# templog2.net
KiCad netlist of a schematic drawn in EAGLE
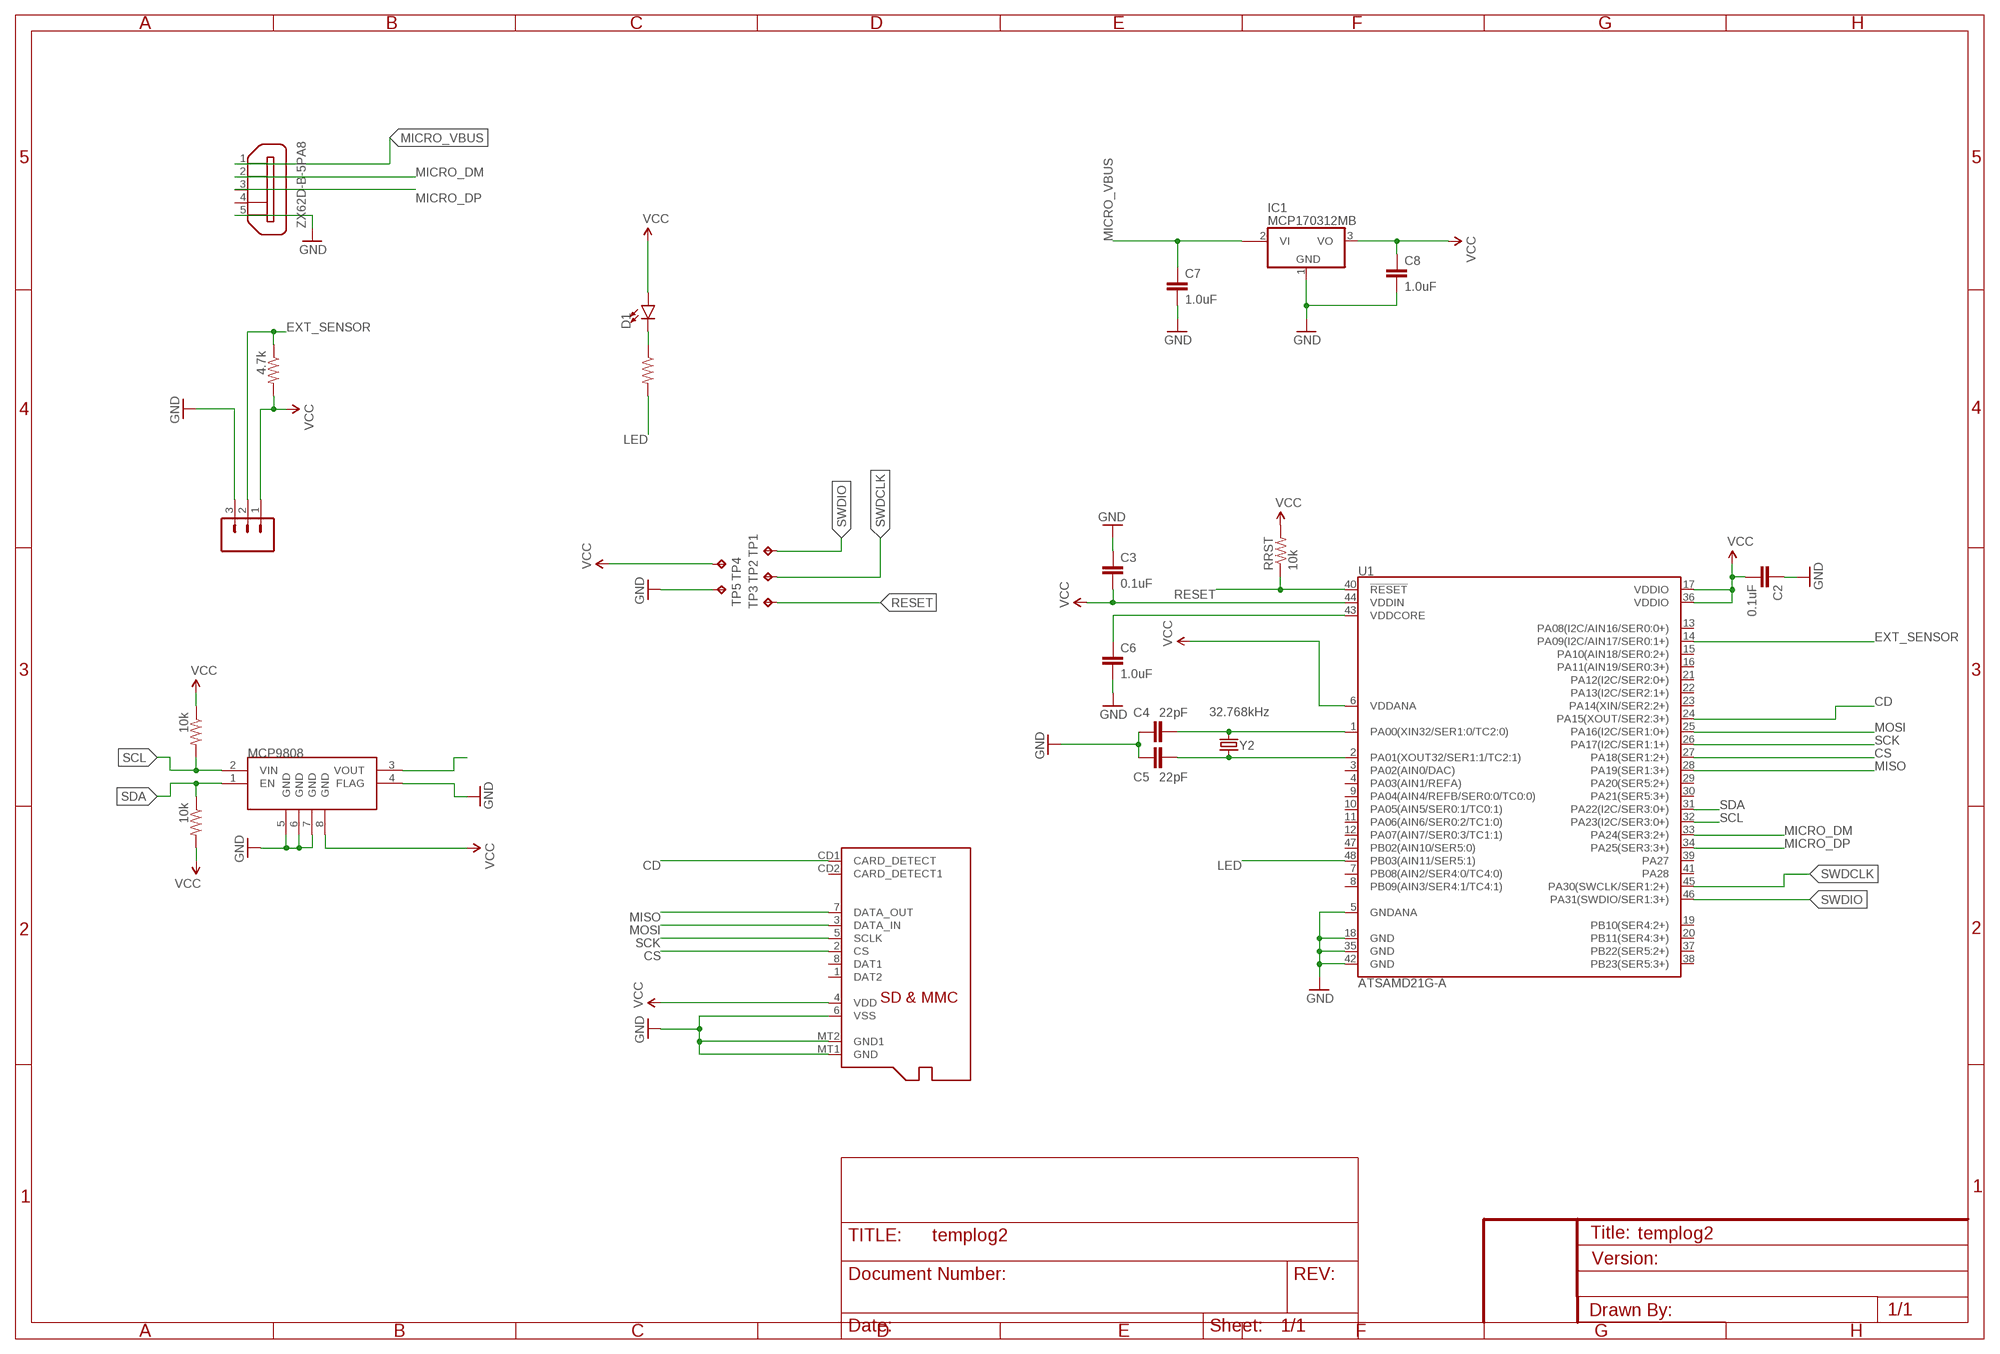
[diagram p0: schematic, sheet 1]

(export (version "E")
  (design (tool "Eeschema 10.0.6"))
  (components
    (comp (ref "C2")
      (value "0.1uF")
      (footprint "eagle-import:0805")
      (libsource (lib "eagle-import") (part "1.0UF-0805-25V-10%"))
    )
    (comp (ref "C3")
      (value "0.1uF")
      (footprint "eagle-import:0805")
      (libsource (lib "eagle-import") (part "1.0UF-0805-25V-10%"))
    )
    (comp (ref "C4")
      (value "22pF")
      (footprint "eagle-import:0805")
      (libsource (lib "eagle-import") (part "CAP0805"))
    )
    (comp (ref "C5")
      (value "22pF")
      (footprint "eagle-import:0805")
      (libsource (lib "eagle-import") (part "CAP0805"))
    )
    (comp (ref "C6")
      (value "1.0uF")
      (footprint "eagle-import:0805")
      (libsource (lib "eagle-import") (part "1.0UF-0805-25V-10%"))
    )
    (comp (ref "C7")
      (value "1.0uF")
      (footprint "eagle-import:0805")
      (libsource (lib "eagle-import") (part "1.0UF-0805-25V-10%"))
    )
    (comp (ref "C8")
      (value "1.0uF")
      (footprint "eagle-import:0805")
      (libsource (lib "eagle-import") (part "1.0UF-0805-25V-10%"))
    )
    (comp (ref "D1")
      (value "LED1206")
      (footprint "eagle-import:LED-1206")
      (libsource (lib "eagle-import") (part "LED1206"))
    )
    (comp (ref "IC1")
      (value "MCP170312MB")
      (footprint "eagle-import:SOT89")
      (libsource (lib "eagle-import") (part "MCP1703MB12"))
    )
    (comp (ref "J2")
      (value "CONN_03SMD")
      (footprint "eagle-import:1X03-1MM-RA")
      (libsource (lib "eagle-import") (part "CONN_03SMD"))
    )
    (comp (ref "MCP9808")
      (value "V_REG_MIC5216")
      (footprint "eagle-import:MSOP8")
      (libsource (lib "eagle-import") (part "V_REG_MIC5216"))
    )
    (comp (ref "RRST")
      (value "10k")
      (footprint "eagle-import:0805")
      (libsource (lib "eagle-import") (part "RESISTOR0805-RES"))
    )
    (comp (ref "R_I2C_1")
      (value "10k")
      (footprint "eagle-import:0805")
      (libsource (lib "eagle-import") (part "RESISTOR0805-RES"))
    )
    (comp (ref "R_I2C_2")
      (value "10k")
      (footprint "eagle-import:0805")
      (libsource (lib "eagle-import") (part "RESISTOR0805-RES"))
    )
    (comp (ref "R_I2C_3")
      (value "4.7k")
      (footprint "eagle-import:0805")
      (libsource (lib "eagle-import") (part "RESISTOR0805-RES"))
    )
    (comp (ref "R_I2C_4")
      (value "RESISTOR0805-RES")
      (footprint "eagle-import:0805")
      (libsource (lib "eagle-import") (part "RESISTOR0805-RES"))
    )
    (comp (ref "TP1")
      (value "TPB1,27")
      (footprint "eagle-import:B1,27")
      (libsource (lib "eagle-import") (part "TPB1,27"))
    )
    (comp (ref "TP2")
      (value "TPB1,27")
      (footprint "eagle-import:B1,27")
      (libsource (lib "eagle-import") (part "TPB1,27"))
    )
    (comp (ref "TP3")
      (value "TPB1,27")
      (footprint "eagle-import:B1,27")
      (libsource (lib "eagle-import") (part "TPB1,27"))
    )
    (comp (ref "TP4")
      (value "TPB1,27")
      (footprint "eagle-import:B1,27")
      (libsource (lib "eagle-import") (part "TPB1,27"))
    )
    (comp (ref "TP5")
      (value "TPB1,27")
      (footprint "eagle-import:B1,27")
      (libsource (lib "eagle-import") (part "TPB1,27"))
    )
    (comp (ref "U$1")
      (value "MICROSD")
      (footprint "eagle-import:MICROSD")
      (libsource (lib "eagle-import") (part "MICROSD"))
    )
    (comp (ref "U1")
      (value "ATSAMD21G-A")
      (footprint "eagle-import:TQFP-48")
      (libsource (lib "eagle-import") (part "ATSAMD21G-A"))
    )
    (comp (ref "X2")
      (value "ZX62D-B-5PA8")
      (footprint "eagle-import:ZX62D-B-5PA8")
      (fields (field (name "MF") "Hirose"))
      (libsource (lib "eagle-import") (part "ZX62D-B-5PA8"))
    )
    (comp (ref "Y2")
      (value "32.768kHz")
      (footprint "eagle-import:CRYSTAL-SMD-3.2X1.5MM")
      (libsource (lib "eagle-import") (part "CRYSTAL3.2X1.5MM"))
    )
  )
  (nets
    (net (code "1") (name "/CD") (class "Default")
      (node (ref "U$1") (pin "CD1") (pinfunction "CARD_DETECT_CD1") (pintype "passive"))
      (node (ref "U1") (pin "24") (pinfunction "PA15(XOUT/SER2:3+)_24") (pintype "bidirectional"))
    )
    (net (code "2") (name "/CS") (class "Default")
      (node (ref "U$1") (pin "2") (pinfunction "CS_2") (pintype "input"))
      (node (ref "U1") (pin "27") (pinfunction "PA18(SER1:2+)_27") (pintype "bidirectional"))
    )
    (net (code "3") (name "/EXT_SENSOR") (class "Default")
      (node (ref "J2") (pin "2") (pinfunction "2_2") (pintype "passive"))
      (node (ref "R_I2C_3") (pin "1") (pinfunction "1_1") (pintype "passive"))
      (node (ref "U1") (pin "14") (pinfunction "PA09(I2C/AIN17/SER0:1+)_14") (pintype "bidirectional"))
    )
    (net (code "4") (name "/LED") (class "Default")
      (node (ref "R_I2C_4") (pin "2") (pinfunction "2_2") (pintype "passive"))
      (node (ref "U1") (pin "48") (pinfunction "PB03(AIN11/SER5:1)_48") (pintype "bidirectional"))
    )
    (net (code "5") (name "/MICRO_DM") (class "Default")
      (node (ref "U1") (pin "33") (pinfunction "PA24(SER3:2+)_33") (pintype "bidirectional"))
      (node (ref "X2") (pin "2") (pinfunction "2_2") (pintype "passive"))
    )
    (net (code "6") (name "/MICRO_DP") (class "Default")
      (node (ref "U1") (pin "34") (pinfunction "PA25(SER3:3+)_34") (pintype "bidirectional"))
      (node (ref "X2") (pin "3") (pinfunction "3_3") (pintype "passive"))
    )
    (net (code "7") (name "/MISO") (class "Default")
      (node (ref "U$1") (pin "7") (pinfunction "DATA_OUT_7") (pintype "output"))
      (node (ref "U1") (pin "28") (pinfunction "PA19(SER1:3+)_28") (pintype "bidirectional"))
    )
    (net (code "8") (name "/MOSI") (class "Default")
      (node (ref "U$1") (pin "3") (pinfunction "DATA_IN_3") (pintype "input"))
      (node (ref "U1") (pin "25") (pinfunction "PA16(I2C/SER1:0+)_25") (pintype "bidirectional"))
    )
    (net (code "9") (name "/SCK") (class "Default")
      (node (ref "U$1") (pin "5") (pinfunction "SCLK_5") (pintype "input"))
      (node (ref "U1") (pin "26") (pinfunction "PA17(I2C/SER1:1+)_26") (pintype "bidirectional"))
    )
    (net (code "10") (name "GND") (class "Default")
      (node (ref "C2") (pin "1") (pinfunction "1_1") (pintype "passive"))
      (node (ref "C3") (pin "1") (pinfunction "1_1") (pintype "passive"))
      (node (ref "C4") (pin "1") (pinfunction "1_1") (pintype "passive"))
      (node (ref "C5") (pin "1") (pinfunction "1_1") (pintype "passive"))
      (node (ref "C6") (pin "2") (pinfunction "2_2") (pintype "passive"))
      (node (ref "C7") (pin "2") (pinfunction "2_2") (pintype "passive"))
      (node (ref "C8") (pin "2") (pinfunction "2_2") (pintype "passive"))
      (node (ref "IC1") (pin "1") (pinfunction "GND_1") (pintype "passive"))
      (node (ref "J2") (pin "3") (pinfunction "3_3") (pintype "passive"))
      (node (ref "MCP9808") (pin "4") (pinfunction "FLAG_4") (pintype "bidirectional"))
      (node (ref "MCP9808") (pin "5") (pinfunction "GND_5") (pintype "bidirectional"))
      (node (ref "MCP9808") (pin "6") (pinfunction "GND_6") (pintype "bidirectional"))
      (node (ref "MCP9808") (pin "7") (pinfunction "GND_7") (pintype "bidirectional"))
      (node (ref "TP5") (pin "TP") (pinfunction "TP_TP") (pintype "input"))
      (node (ref "U$1") (pin "6") (pinfunction "VSS_6") (pintype "power_in"))
      (node (ref "U$1") (pin "MT1") (pinfunction "GND_MT1") (pintype "power_in"))
      (node (ref "U$1") (pin "MT2") (pinfunction "GND1_MT2") (pintype "power_in"))
      (node (ref "U1") (pin "18") (pinfunction "GND_18") (pintype "bidirectional"))
      (node (ref "U1") (pin "35") (pinfunction "GND_35") (pintype "bidirectional"))
      (node (ref "U1") (pin "42") (pinfunction "GND_42") (pintype "bidirectional"))
      (node (ref "U1") (pin "5") (pinfunction "GNDANA_5") (pintype "bidirectional"))
      (node (ref "X2") (pin "5") (pinfunction "5_5") (pintype "passive"))
    )
    (net (code "11") (name "MICRO_VBUS") (class "Default")
      (node (ref "C7") (pin "1") (pinfunction "1_1") (pintype "passive"))
      (node (ref "IC1") (pin "2@1") (pinfunction "VI1_2@1") (pintype "input"))
      (node (ref "X2") (pin "1") (pinfunction "1_1") (pintype "passive"))
    )
    (net (code "12") (name "Net-(D1-PadC)") (class "Default")
      (node (ref "D1") (pin "C") (pinfunction "C_C") (pintype "passive"))
      (node (ref "R_I2C_4") (pin "1") (pinfunction "1_1") (pintype "passive"))
    )
    (net (code "13") (name "Net-(U1-PA00(XIN32{slash}SER1:0{slash}TC2:0))") (class "Default")
      (node (ref "C4") (pin "2") (pinfunction "2_2") (pintype "passive"))
      (node (ref "U1") (pin "1") (pinfunction "PA00(XIN32/SER1:0/TC2:0)_1") (pintype "bidirectional"))
      (node (ref "Y2") (pin "P$2") (pinfunction "2_P$2") (pintype "passive"))
    )
    (net (code "14") (name "Net-(U1-PA01(XOUT32{slash}SER1:1{slash}TC2:1))") (class "Default")
      (node (ref "C5") (pin "2") (pinfunction "2_2") (pintype "passive"))
      (node (ref "U1") (pin "2") (pinfunction "PA01(XOUT32/SER1:1/TC2:1)_2") (pintype "bidirectional"))
      (node (ref "Y2") (pin "P$1") (pinfunction "1_P$1") (pintype "passive"))
    )
    (net (code "15") (name "Net-(U1-VDDCORE)") (class "Default")
      (node (ref "C6") (pin "1") (pinfunction "1_1") (pintype "passive"))
      (node (ref "U1") (pin "43") (pinfunction "VDDCORE_43") (pintype "bidirectional"))
    )
    (net (code "16") (name "RESET") (class "Default")
      (node (ref "RRST") (pin "1") (pinfunction "1_1") (pintype "passive"))
      (node (ref "TP3") (pin "TP") (pinfunction "TP_TP") (pintype "input"))
      (node (ref "U1") (pin "40") (pinfunction "~{RESET}_40") (pintype "bidirectional"))
    )
    (net (code "17") (name "SCL") (class "Default")
      (node (ref "MCP9808") (pin "2") (pinfunction "VIN_2") (pintype "bidirectional"))
      (node (ref "R_I2C_1") (pin "2") (pinfunction "2_2") (pintype "passive"))
      (node (ref "U1") (pin "32") (pinfunction "PA23(I2C/SER3:0+)_32") (pintype "bidirectional"))
    )
    (net (code "18") (name "SDA") (class "Default")
      (node (ref "MCP9808") (pin "1") (pinfunction "EN_1") (pintype "bidirectional"))
      (node (ref "R_I2C_2") (pin "1") (pinfunction "1_1") (pintype "passive"))
      (node (ref "U1") (pin "31") (pinfunction "PA22(I2C/SER3:0+)_31") (pintype "bidirectional"))
    )
    (net (code "19") (name "SWDCLK") (class "Default")
      (node (ref "TP2") (pin "TP") (pinfunction "TP_TP") (pintype "input"))
      (node (ref "U1") (pin "45") (pinfunction "PA30(SWCLK/SER1:2+)_45") (pintype "bidirectional"))
    )
    (net (code "20") (name "SWDIO") (class "Default")
      (node (ref "TP1") (pin "TP") (pinfunction "TP_TP") (pintype "input"))
      (node (ref "U1") (pin "46") (pinfunction "PA31(SWDIO/SER1:3+)_46") (pintype "bidirectional"))
    )
    (net (code "21") (name "VCC") (class "Default")
      (node (ref "C2") (pin "2") (pinfunction "2_2") (pintype "passive"))
      (node (ref "C3") (pin "2") (pinfunction "2_2") (pintype "passive"))
      (node (ref "C8") (pin "1") (pinfunction "1_1") (pintype "passive"))
      (node (ref "D1") (pin "A") (pinfunction "A_A") (pintype "passive"))
      (node (ref "IC1") (pin "3") (pinfunction "VO_3") (pintype "passive"))
      (node (ref "J2") (pin "1") (pinfunction "1_1") (pintype "passive"))
      (node (ref "MCP9808") (pin "8") (pinfunction "GND_8") (pintype "bidirectional"))
      (node (ref "RRST") (pin "2") (pinfunction "2_2") (pintype "passive"))
      (node (ref "R_I2C_1") (pin "1") (pinfunction "1_1") (pintype "passive"))
      (node (ref "R_I2C_2") (pin "2") (pinfunction "2_2") (pintype "passive"))
      (node (ref "R_I2C_3") (pin "2") (pinfunction "2_2") (pintype "passive"))
      (node (ref "TP4") (pin "TP") (pinfunction "TP_TP") (pintype "input"))
      (node (ref "U$1") (pin "4") (pinfunction "VDD_4") (pintype "power_in"))
      (node (ref "U1") (pin "17") (pinfunction "VDDIO_17") (pintype "bidirectional"))
      (node (ref "U1") (pin "36") (pinfunction "VDDIO_36") (pintype "bidirectional"))
      (node (ref "U1") (pin "44") (pinfunction "VDDIN_44") (pintype "bidirectional"))
      (node (ref "U1") (pin "6") (pinfunction "VDDANA_6") (pintype "bidirectional"))
    )
    (net (code "22") (name "unconnected-(IC1-VI-Pad2)") (class "Default")
      (node (ref "IC1") (pin "2") (pinfunction "VI_2") (pintype "input"))
    )
    (net (code "23") (name "unconnected-(MCP9808-VOUT-Pad3)") (class "Default")
      (node (ref "MCP9808") (pin "3") (pinfunction "VOUT_3") (pintype "bidirectional"))
    )
    (net (code "24") (name "unconnected-(U$1-CARD_DETECT1-PadCD2)") (class "Default")
      (node (ref "U$1") (pin "CD2") (pinfunction "CARD_DETECT1_CD2") (pintype "passive"))
    )
    (net (code "25") (name "unconnected-(U$1-DAT1-Pad8)") (class "Default")
      (node (ref "U$1") (pin "8") (pinfunction "DAT1_8") (pintype "bidirectional"))
    )
    (net (code "26") (name "unconnected-(U$1-DAT2-Pad1)") (class "Default")
      (node (ref "U$1") (pin "1") (pinfunction "DAT2_1") (pintype "bidirectional"))
    )
    (net (code "27") (name "unconnected-(U1-PA02(AIN0{slash}DAC)-Pad3)") (class "Default")
      (node (ref "U1") (pin "3") (pinfunction "PA02(AIN0/DAC)_3") (pintype "bidirectional"))
    )
    (net (code "28") (name "unconnected-(U1-PA03(AIN1{slash}REFA)-Pad4)") (class "Default")
      (node (ref "U1") (pin "4") (pinfunction "PA03(AIN1/REFA)_4") (pintype "bidirectional"))
    )
    (net (code "29") (name "unconnected-(U1-PA04(AIN4{slash}REFB{slash}SER0:0{slash}TC0:0)-Pad9)") (class "Default")
      (node (ref "U1") (pin "9") (pinfunction "PA04(AIN4/REFB/SER0:0/TC0:0)_9") (pintype "bidirectional"))
    )
    (net (code "30") (name "unconnected-(U1-PA05(AIN5{slash}SER0:1{slash}TC0:1)-Pad10)") (class "Default")
      (node (ref "U1") (pin "10") (pinfunction "PA05(AIN5/SER0:1/TC0:1)_10") (pintype "bidirectional"))
    )
    (net (code "31") (name "unconnected-(U1-PA06(AIN6{slash}SER0:2{slash}TC1:0)-Pad11)") (class "Default")
      (node (ref "U1") (pin "11") (pinfunction "PA06(AIN6/SER0:2/TC1:0)_11") (pintype "bidirectional"))
    )
    (net (code "32") (name "unconnected-(U1-PA07(AIN7{slash}SER0:3{slash}TC1:1)-Pad12)") (class "Default")
      (node (ref "U1") (pin "12") (pinfunction "PA07(AIN7/SER0:3/TC1:1)_12") (pintype "bidirectional"))
    )
    (net (code "33") (name "unconnected-(U1-PA08(I2C{slash}AIN16{slash}SER0:0+)-Pad13)") (class "Default")
      (node (ref "U1") (pin "13") (pinfunction "PA08(I2C/AIN16/SER0:0+)_13") (pintype "bidirectional"))
    )
    (net (code "34") (name "unconnected-(U1-PA10(AIN18{slash}SER0:2+)-Pad15)") (class "Default")
      (node (ref "U1") (pin "15") (pinfunction "PA10(AIN18/SER0:2+)_15") (pintype "bidirectional"))
    )
    (net (code "35") (name "unconnected-(U1-PA11(AIN19{slash}SER0:3+)-Pad16)") (class "Default")
      (node (ref "U1") (pin "16") (pinfunction "PA11(AIN19/SER0:3+)_16") (pintype "bidirectional"))
    )
    (net (code "36") (name "unconnected-(U1-PA12(I2C{slash}SER2:0+)-Pad21)") (class "Default")
      (node (ref "U1") (pin "21") (pinfunction "PA12(I2C/SER2:0+)_21") (pintype "bidirectional"))
    )
    (net (code "37") (name "unconnected-(U1-PA13(I2C{slash}SER2:1+)-Pad22)") (class "Default")
      (node (ref "U1") (pin "22") (pinfunction "PA13(I2C/SER2:1+)_22") (pintype "bidirectional"))
    )
    (net (code "38") (name "unconnected-(U1-PA14(XIN{slash}SER2:2+)-Pad23)") (class "Default")
      (node (ref "U1") (pin "23") (pinfunction "PA14(XIN/SER2:2+)_23") (pintype "bidirectional"))
    )
    (net (code "39") (name "unconnected-(U1-PA20(SER5:2+)-Pad29)") (class "Default")
      (node (ref "U1") (pin "29") (pinfunction "PA20(SER5:2+)_29") (pintype "bidirectional"))
    )
    (net (code "40") (name "unconnected-(U1-PA21(SER5:3+)-Pad30)") (class "Default")
      (node (ref "U1") (pin "30") (pinfunction "PA21(SER5:3+)_30") (pintype "bidirectional"))
    )
    (net (code "41") (name "unconnected-(U1-PA27-Pad39)") (class "Default")
      (node (ref "U1") (pin "39") (pinfunction "PA27_39") (pintype "bidirectional"))
    )
    (net (code "42") (name "unconnected-(U1-PA28-Pad41)") (class "Default")
      (node (ref "U1") (pin "41") (pinfunction "PA28_41") (pintype "bidirectional"))
    )
    (net (code "43") (name "unconnected-(U1-PB02(AIN10{slash}SER5:0)-Pad47)") (class "Default")
      (node (ref "U1") (pin "47") (pinfunction "PB02(AIN10/SER5:0)_47") (pintype "bidirectional"))
    )
    (net (code "44") (name "unconnected-(U1-PB08(AIN2{slash}SER4:0{slash}TC4:0)-Pad7)") (class "Default")
      (node (ref "U1") (pin "7") (pinfunction "PB08(AIN2/SER4:0/TC4:0)_7") (pintype "bidirectional"))
    )
    (net (code "45") (name "unconnected-(U1-PB09(AIN3{slash}SER4:1{slash}TC4:1)-Pad8)") (class "Default")
      (node (ref "U1") (pin "8") (pinfunction "PB09(AIN3/SER4:1/TC4:1)_8") (pintype "bidirectional"))
    )
    (net (code "46") (name "unconnected-(U1-PB10(SER4:2+)-Pad19)") (class "Default")
      (node (ref "U1") (pin "19") (pinfunction "PB10(SER4:2+)_19") (pintype "bidirectional"))
    )
    (net (code "47") (name "unconnected-(U1-PB11(SER4:3+)-Pad20)") (class "Default")
      (node (ref "U1") (pin "20") (pinfunction "PB11(SER4:3+)_20") (pintype "bidirectional"))
    )
    (net (code "48") (name "unconnected-(U1-PB22(SER5:2+)-Pad37)") (class "Default")
      (node (ref "U1") (pin "37") (pinfunction "PB22(SER5:2+)_37") (pintype "bidirectional"))
    )
    (net (code "49") (name "unconnected-(U1-PB23(SER5:3+)-Pad38)") (class "Default")
      (node (ref "U1") (pin "38") (pinfunction "PB23(SER5:3+)_38") (pintype "bidirectional"))
    )
    (net (code "50") (name "unconnected-(X2-Pad4)") (class "Default")
      (node (ref "X2") (pin "4") (pinfunction "4_4") (pintype "passive"))
    )
  )
)
